# PwrConfig.net
KiCad netlist of a schematic drawn in Altium Designer
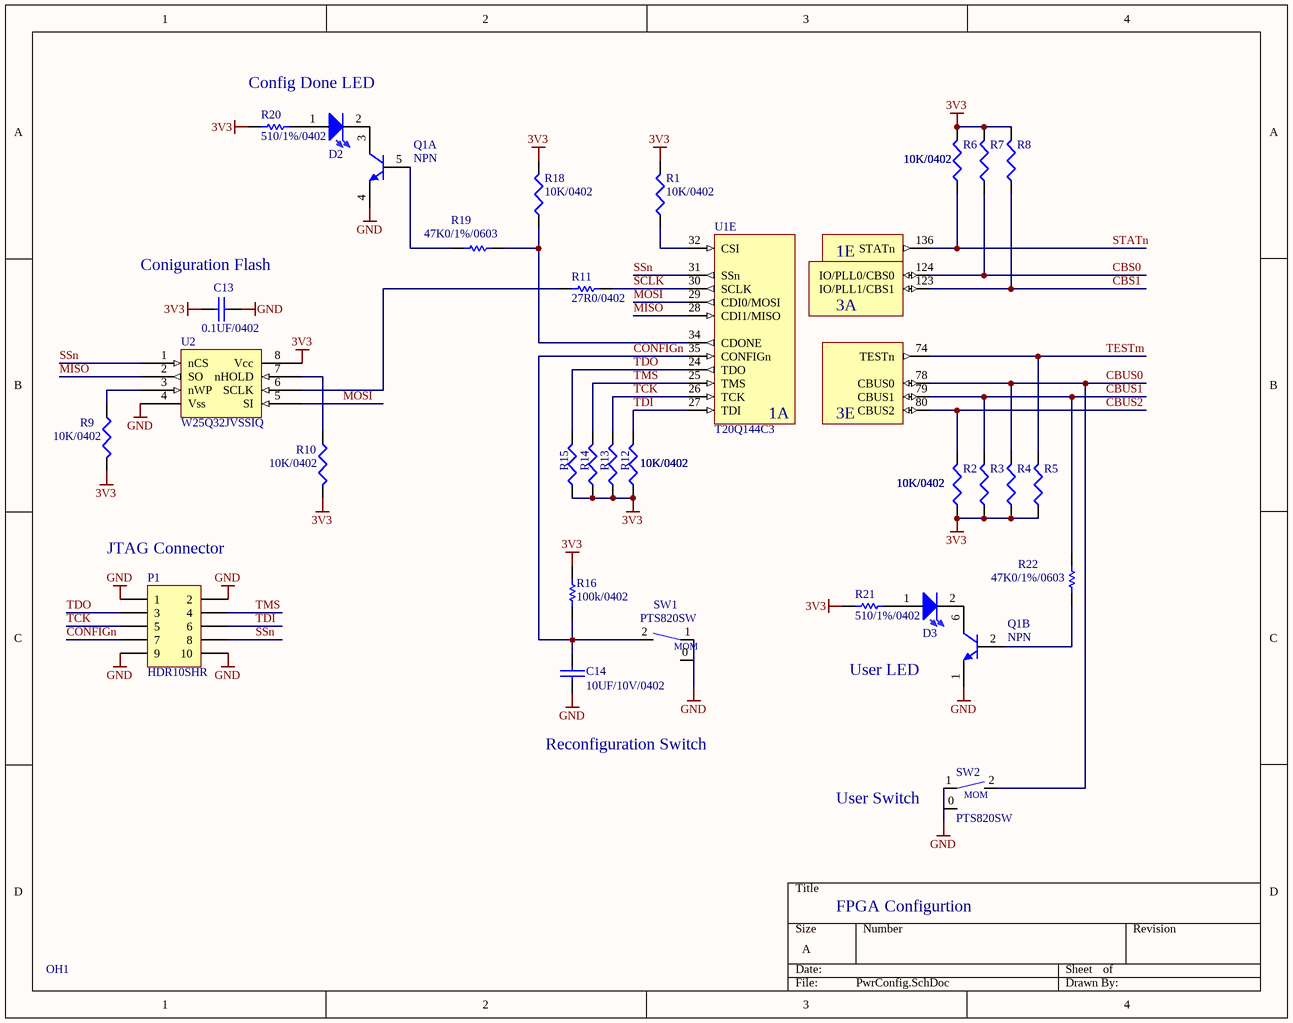
[diagram p0: PwrConfig.SchDoc]

(export (version "E")
  (design (tool "Eeschema 10.0.6"))
  (components
    (comp (ref "C13")
      (value "0.1UF/0402")
      (footprint "0402")
      (description "±10% 16V Ceramic Capacitor X7R 0402 (1005 Metric)")
      (fields (field (name "MFG") "TDK"))
      (libsource (lib "Capacitors") (part "0.1UF/16v/0402"))
    )
    (comp (ref "C14")
      (value "10UF/10V/0402")
      (footprint "0402")
      (description "±20% 10V Ceramic Capacitor X5R 0402 (1005 Metric)")
      (fields (field (name "MFG") "Samsung"))
      (libsource (lib "Capacitors") (part "10UF/10V/0402"))
    )
    (comp (ref "D2")
      (value "LTST-C191KGKT")
      (footprint "LED0603")
      (description "Green 571nm LED Indication - Discrete 2V 0603 (1608 Metric)")
      (fields (field (name "MFG") "Liteon"))
      (libsource (lib "MiscSemi") (part "LTST-C191KGKT"))
    )
    (comp (ref "D3")
      (value "LTST-C191KGKT")
      (footprint "LED0603")
      (description "Green 571nm LED Indication - Discrete 2V 0603 (1608 Metric)")
      (fields (field (name "MFG") "Liteon"))
      (libsource (lib "MiscSemi") (part "LTST-C191KGKT"))
    )
    (comp (ref "OH1") (value "OPENHW_SCH") (libsource (lib "Misc") (part "OPENHW_SCH")))
    (comp (ref "P1")
      (value "HDR10SHR")
      (footprint "HDR10")
      (description "Connector Header Through Hole 10 position 0.100\" (2.54mm)")
      (fields (field (name "MFG") "On Shore"))
      (libsource (lib "Connectors") (part "HDR10SHR"))
    )
    (comp (ref "Q1")
      (value "NPN")
      (footprint "SC70-6_HAND")
      (fields (field (name "MFG") "On Semi"))
      (libsource (lib "MiscSemi") (part "MBT3904DW1T1G"))
    )
    (comp (ref "R1")
      (value "10K/0402")
      (footprint "0402")
      (fields (field (name "MFG") "Yaego"))
      (libsource (lib "Resistors") (part "10K/0402"))
    )
    (comp (ref "R2")
      (value "10K/0402")
      (footprint "0402")
      (fields (field (name "MFG") "Yaego"))
      (libsource (lib "Resistors") (part "10K/0402"))
    )
    (comp (ref "R3")
      (value "10K/0402")
      (footprint "0402")
      (fields (field (name "MFG") "Yaego"))
      (libsource (lib "Resistors") (part "10K/0402"))
    )
    (comp (ref "R4")
      (value "10K/0402")
      (footprint "0402")
      (fields (field (name "MFG") "Yaego"))
      (libsource (lib "Resistors") (part "10K/0402"))
    )
    (comp (ref "R5")
      (value "10K/0402")
      (footprint "0402")
      (fields (field (name "MFG") "Yaego"))
      (libsource (lib "Resistors") (part "10K/0402"))
    )
    (comp (ref "R6")
      (value "10K/0402")
      (footprint "0402")
      (fields (field (name "MFG") "Yaego"))
      (libsource (lib "Resistors") (part "10K/0402"))
    )
    (comp (ref "R7")
      (value "10K/0402")
      (footprint "0402")
      (fields (field (name "MFG") "Yaego"))
      (libsource (lib "Resistors") (part "10K/0402"))
    )
    (comp (ref "R8")
      (value "10K/0402")
      (footprint "0402")
      (fields (field (name "MFG") "Yaego"))
      (libsource (lib "Resistors") (part "10K/0402"))
    )
    (comp (ref "R9")
      (value "10K/0402")
      (footprint "0402")
      (fields (field (name "MFG") "Yaego"))
      (libsource (lib "Resistors") (part "10K/0402"))
    )
    (comp (ref "R10")
      (value "10K/0402")
      (footprint "0402")
      (fields (field (name "MFG") "Yaego"))
      (libsource (lib "Resistors") (part "10K/0402"))
    )
    (comp (ref "R11")
      (value "27R0/0402")
      (footprint "0402")
      (description "27 Ohms ±1% 0.063W, 1/16W Chip Resistor 0402 (1005 Metric) Moisture Resistant Thick Film")
      (fields (field (name "MFG") "Yageo"))
      (libsource (lib "Resistors") (part "27R0/0402"))
    )
    (comp (ref "R12")
      (value "10K/0402")
      (footprint "0402")
      (fields (field (name "MFG") "Yaego"))
      (libsource (lib "Resistors") (part "10K/0402"))
    )
    (comp (ref "R13")
      (value "10K/0402")
      (footprint "0402")
      (fields (field (name "MFG") "Yaego"))
      (libsource (lib "Resistors") (part "10K/0402"))
    )
    (comp (ref "R14")
      (value "10K/0402")
      (footprint "0402")
      (fields (field (name "MFG") "Yaego"))
      (libsource (lib "Resistors") (part "10K/0402"))
    )
    (comp (ref "R15")
      (value "10K/0402")
      (footprint "0402")
      (fields (field (name "MFG") "Yaego"))
      (libsource (lib "Resistors") (part "10K/0402"))
    )
    (comp (ref "R16")
      (value "100k/0402")
      (footprint "0402")
      (description "100 kOhms ±1% 0.063W, 1/16W Chip Resistor 0402 (1005 Metric) Automotive AEC-Q200 Thick Film")
      (fields (field (name "MFG") "Stackpole"))
      (libsource (lib "Resistors") (part "100k/0402"))
    )
    (comp (ref "R18")
      (value "10K/0402")
      (footprint "0402")
      (fields (field (name "MFG") "Yaego"))
      (libsource (lib "Resistors") (part "10K/0402"))
    )
    (comp (ref "R19")
      (value "47K0/1%/0603")
      (footprint "0402")
      (description "47 kOhms ±1% 0.063W, 1/16W Chip Resistor 0402 (1005 Metric) Moisture Resistant Thick Film")
      (fields (field (name "MFG") "Yageo"))
      (libsource (lib "Resistors") (part "RES1K00_1"))
    )
    (comp (ref "R20")
      (value "510/1%/0402")
      (footprint "0402")
      (description "510 Ohms ±1% 0.063W, 1/16W Chip Resistor 0402 (1005 Metric) Moisture Resistant Thick Film")
      (fields (field (name "MFG") "Yageo"))
      (libsource (lib "Resistors") (part "510/1%/0402"))
    )
    (comp (ref "R21")
      (value "510/1%/0402")
      (footprint "0402")
      (description "510 Ohms ±1% 0.063W, 1/16W Chip Resistor 0402 (1005 Metric) Moisture Resistant Thick Film")
      (fields (field (name "MFG") "Yageo"))
      (libsource (lib "Resistors") (part "510/1%/0402"))
    )
    (comp (ref "R22")
      (value "47K0/1%/0603")
      (footprint "0402")
      (description "47 kOhms ±1% 0.063W, 1/16W Chip Resistor 0402 (1005 Metric) Moisture Resistant Thick Film")
      (fields (field (name "MFG") "Yageo"))
      (libsource (lib "Resistors") (part "RES1K00_1"))
    )
    (comp (ref "SW1")
      (value "PTS820SW")
      (footprint "PTS820")
      (description "Tactile Switch SPST-NO Top Actuated Surface Mount")
      (fields (field (name "MFG") "C&K"))
      (libsource (lib "Misc") (part "PTS820SW"))
    )
    (comp (ref "SW2")
      (value "PTS820SW")
      (footprint "PTS820")
      (description "Tactile Switch SPST-NO Top Actuated Surface Mount")
      (fields (field (name "MFG") "C&K"))
      (libsource (lib "Misc") (part "PTS820SW"))
    )
    (comp (ref "U1")
      (value "T20Q144C3")
      (footprint "LQFP144")
      (description "Trion® Field Programmable Gate Array (FPGA) IC 97 1044 19728 144-LQFP")
      (fields (field (name "MFG") "Efinix"))
      (libsource (lib "DigitalIC") (part "T20Q144C3"))
    )
    (comp (ref "U2")
      (value "W25Q32JVSSIQ")
      (footprint "so8w")
      (description "FLASH - NOR Memory IC 32Mb (4M x 8) SPI - Quad I/O 133 MHz 8-SOIC")
      (fields (field (name "MFG") "Winbond"))
      (libsource (lib "DigitalIC") (part "W25Q32JVSSIQ"))
    )
  )
  (nets
    (net (code "1") (name "/CBS0") (class "Default")
      (node (ref "R7") (pin "1") (pintype "passive"))
      (node (ref "U1") (pin "124") (pinfunction "IO/PLL0/CBS0_124") (pintype "bidirectional"))
    )
    (net (code "2") (name "/CBS1") (class "Default")
      (node (ref "R8") (pin "1") (pintype "passive"))
      (node (ref "U1") (pin "123") (pinfunction "IO/PLL1/CBS1_123") (pintype "bidirectional"))
    )
    (net (code "3") (name "/CBUS0") (class "Default")
      (node (ref "R4") (pin "2") (pintype "passive"))
      (node (ref "SW2") (pin "2") (pinfunction "2_2") (pintype "passive"))
      (node (ref "U1") (pin "78") (pinfunction "CBUS0_78") (pintype "bidirectional"))
    )
    (net (code "4") (name "/CBUS1") (class "Default")
      (node (ref "R22") (pin "2") (pinfunction "2_2") (pintype "passive"))
      (node (ref "R3") (pin "2") (pintype "passive"))
      (node (ref "U1") (pin "79") (pinfunction "CBUS1_79") (pintype "bidirectional"))
    )
    (net (code "5") (name "/CBUS2") (class "Default")
      (node (ref "R2") (pin "2") (pintype "passive"))
      (node (ref "U1") (pin "80") (pinfunction "CBUS2_80") (pintype "bidirectional"))
    )
    (net (code "6") (name "/CONFIGn") (class "Default")
      (node (ref "C14") (pin "1") (pintype "passive"))
      (node (ref "P1") (pin "7") (pinfunction "7_7") (pintype "passive"))
      (node (ref "R16") (pin "1") (pinfunction "1_1") (pintype "passive"))
      (node (ref "SW1") (pin "2") (pinfunction "2_2") (pintype "passive"))
      (node (ref "U1") (pin "35") (pinfunction "CONFIGn_35") (pintype "input"))
    )
    (net (code "7") (name "/MISO") (class "Default")
      (node (ref "U1") (pin "28") (pinfunction "CDI1/MISO_28") (pintype "input"))
      (node (ref "U2") (pin "2") (pinfunction "SO_2") (pintype "output"))
    )
    (net (code "8") (name "/MOSI") (class "Default")
      (node (ref "U1") (pin "29") (pinfunction "CDI0/MOSI_29") (pintype "output"))
      (node (ref "U2") (pin "5") (pinfunction "SI_5") (pintype "input"))
    )
    (net (code "9") (name "/SCLK") (class "Default")
      (node (ref "R11") (pin "1") (pinfunction "1_1") (pintype "passive"))
      (node (ref "U1") (pin "30") (pinfunction "SCLK_30") (pintype "output"))
    )
    (net (code "10") (name "/SSn") (class "Default")
      (node (ref "P1") (pin "8") (pinfunction "8_8") (pintype "passive"))
      (node (ref "U1") (pin "31") (pinfunction "SSn_31") (pintype "output"))
      (node (ref "U2") (pin "1") (pinfunction "nCS_1") (pintype "input"))
    )
    (net (code "11") (name "/STATn") (class "Default")
      (node (ref "R6") (pin "1") (pintype "passive"))
      (node (ref "U1") (pin "136") (pinfunction "STATn_136") (pintype "output"))
    )
    (net (code "12") (name "/TCK") (class "Default")
      (node (ref "P1") (pin "5") (pinfunction "5_5") (pintype "passive"))
      (node (ref "R13") (pin "2") (pintype "passive"))
      (node (ref "U1") (pin "26") (pinfunction "TCK_26") (pintype "input"))
    )
    (net (code "13") (name "/TDI") (class "Default")
      (node (ref "P1") (pin "6") (pinfunction "6_6") (pintype "passive"))
      (node (ref "R12") (pin "2") (pintype "passive"))
      (node (ref "U1") (pin "27") (pinfunction "TDI_27") (pintype "input"))
    )
    (net (code "14") (name "/TDO") (class "Default")
      (node (ref "P1") (pin "3") (pinfunction "3_3") (pintype "passive"))
      (node (ref "R15") (pin "2") (pintype "passive"))
      (node (ref "U1") (pin "24") (pinfunction "TDO_24") (pintype "output"))
    )
    (net (code "15") (name "/TESTm") (class "Default")
      (node (ref "R5") (pin "2") (pintype "passive"))
      (node (ref "U1") (pin "74") (pinfunction "TESTn_74") (pintype "output"))
    )
    (net (code "16") (name "/TMS") (class "Default")
      (node (ref "P1") (pin "4") (pinfunction "4_4") (pintype "passive"))
      (node (ref "R14") (pin "2") (pintype "passive"))
      (node (ref "U1") (pin "25") (pinfunction "TMS_25") (pintype "input"))
    )
    (net (code "17") (name "3V3") (class "Default")
      (node (ref "C13") (pin "2") (pintype "passive"))
      (node (ref "R1") (pin "2") (pintype "passive"))
      (node (ref "R10") (pin "2") (pintype "passive"))
      (node (ref "R12") (pin "1") (pintype "passive"))
      (node (ref "R13") (pin "1") (pintype "passive"))
      (node (ref "R14") (pin "1") (pintype "passive"))
      (node (ref "R15") (pin "1") (pintype "passive"))
      (node (ref "R16") (pin "2") (pinfunction "2_2") (pintype "passive"))
      (node (ref "R18") (pin "2") (pintype "passive"))
      (node (ref "R2") (pin "1") (pintype "passive"))
      (node (ref "R20") (pin "2") (pinfunction "2_2") (pintype "passive"))
      (node (ref "R21") (pin "2") (pinfunction "2_2") (pintype "passive"))
      (node (ref "R3") (pin "1") (pintype "passive"))
      (node (ref "R4") (pin "1") (pintype "passive"))
      (node (ref "R5") (pin "1") (pintype "passive"))
      (node (ref "R6") (pin "2") (pintype "passive"))
      (node (ref "R7") (pin "2") (pintype "passive"))
      (node (ref "R8") (pin "2") (pintype "passive"))
      (node (ref "R9") (pin "2") (pintype "passive"))
      (node (ref "U2") (pin "8") (pinfunction "Vcc_8") (pintype "power_in"))
    )
    (net (code "18") (name "GND") (class "Default")
      (node (ref "C13") (pin "1") (pintype "passive"))
      (node (ref "C14") (pin "2") (pintype "passive"))
      (node (ref "P1") (pin "1") (pinfunction "1_1") (pintype "passive"))
      (node (ref "P1") (pin "10") (pinfunction "10_10") (pintype "passive"))
      (node (ref "P1") (pin "2") (pinfunction "2_2") (pintype "passive"))
      (node (ref "P1") (pin "9") (pinfunction "9_9") (pintype "passive"))
      (node (ref "Q1") (pin "1") (pinfunction "1_1") (pintype "passive"))
      (node (ref "Q1") (pin "4") (pinfunction "4_4") (pintype "passive"))
      (node (ref "SW1") (pin "1") (pinfunction "1_1") (pintype "passive"))
      (node (ref "SW2") (pin "1") (pinfunction "1_1") (pintype "passive"))
      (node (ref "U2") (pin "4") (pinfunction "Vss_4") (pintype "power_in"))
    )
    (net (code "19") (name "Net-(D2-A)") (class "Default")
      (node (ref "D2") (pin "1") (pinfunction "A_1") (pintype "passive"))
      (node (ref "R20") (pin "1") (pinfunction "1_1") (pintype "passive"))
    )
    (net (code "20") (name "Net-(D2-K)") (class "Default")
      (node (ref "D2") (pin "2") (pinfunction "K_2") (pintype "passive"))
      (node (ref "Q1") (pin "3") (pinfunction "3_3") (pintype "passive"))
    )
    (net (code "21") (name "Net-(D3-A)") (class "Default")
      (node (ref "D3") (pin "1") (pinfunction "A_1") (pintype "passive"))
      (node (ref "R21") (pin "1") (pinfunction "1_1") (pintype "passive"))
    )
    (net (code "22") (name "Net-(D3-K)") (class "Default")
      (node (ref "D3") (pin "2") (pinfunction "K_2") (pintype "passive"))
      (node (ref "Q1") (pin "6") (pinfunction "6_6") (pintype "passive"))
    )
    (net (code "23") (name "Net-(Q1-Pad2)") (class "Default")
      (node (ref "Q1") (pin "2") (pinfunction "2_2") (pintype "passive"))
      (node (ref "R22") (pin "1") (pinfunction "1_1") (pintype "passive"))
    )
    (net (code "24") (name "Net-(Q1-Pad5)") (class "Default")
      (node (ref "Q1") (pin "5") (pinfunction "5_5") (pintype "passive"))
      (node (ref "R19") (pin "1") (pinfunction "1_1") (pintype "passive"))
    )
    (net (code "25") (name "Net-(U1E-CDONE)") (class "Default")
      (node (ref "R18") (pin "1") (pintype "passive"))
      (node (ref "R19") (pin "2") (pinfunction "2_2") (pintype "passive"))
      (node (ref "U1") (pin "34") (pinfunction "CDONE_34") (pintype "output"))
    )
    (net (code "26") (name "Net-(U1E-CSI)") (class "Default")
      (node (ref "R1") (pin "1") (pintype "passive"))
      (node (ref "U1") (pin "32") (pinfunction "CSI_32") (pintype "input"))
    )
    (net (code "27") (name "Net-(U2-SCLK)") (class "Default")
      (node (ref "R11") (pin "2") (pinfunction "2_2") (pintype "passive"))
      (node (ref "U2") (pin "6") (pinfunction "SCLK_6") (pintype "input"))
    )
    (net (code "28") (name "Net-(U2-nHOLD)") (class "Default")
      (node (ref "R10") (pin "1") (pintype "passive"))
      (node (ref "U2") (pin "7") (pinfunction "nHOLD_7") (pintype "input"))
    )
    (net (code "29") (name "Net-(U2-nWP)") (class "Default")
      (node (ref "R9") (pin "1") (pintype "passive"))
      (node (ref "U2") (pin "3") (pinfunction "nWP_3") (pintype "input"))
    )
    (net (code "30") (name "unconnected-(SW1-Pad0)") (class "Default")
      (node (ref "SW1") (pin "0") (pinfunction "0_0") (pintype "passive"))
    )
    (net (code "31") (name "unconnected-(SW2-Pad0)") (class "Default")
      (node (ref "SW2") (pin "0") (pinfunction "0_0") (pintype "passive"))
    )
  )
)
